# bela_expansion_card_2.net
KiCad netlist of a schematic drawn in Altium Designer
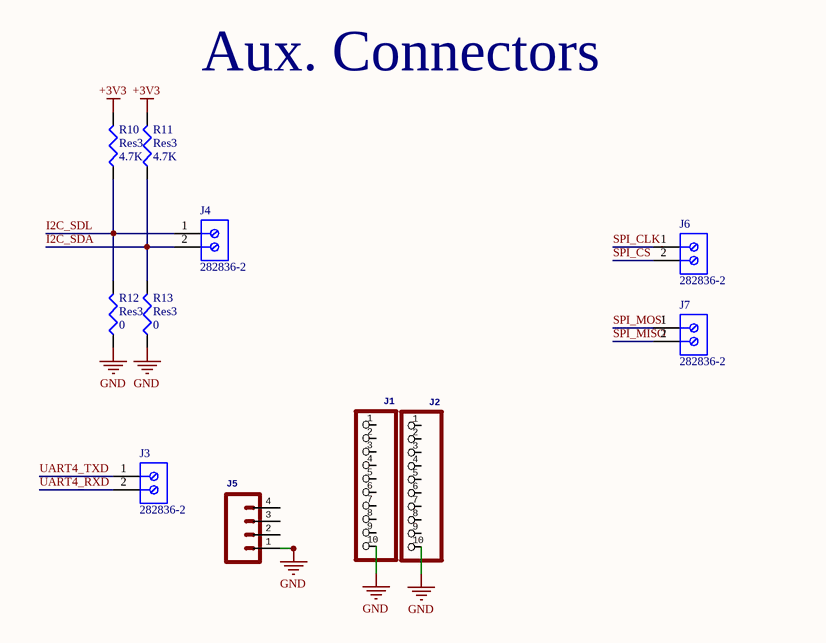
[diagram p0: bela_expansion_card_2.SchDoc]

(export (version "E")
  (design (tool "Eeschema 10.0.6"))
  (components
    (comp (ref "J1")
      (value "PINHD-1X10")
      (footprint "HDR1X10")
      (description "PIN HEADER")
      (fields (field (name "LIBRARYNAME") "pinhead"))
      (libsource (lib "pinhead") (part "PINHD-1X10"))
    )
    (comp (ref "J2")
      (value "PINHD-1X10")
      (footprint "HDR1X10")
      (description "PIN HEADER")
      (fields (field (name "LIBRARYNAME") "pinhead"))
      (libsource (lib "Miscellaneous Connectors") (part "PINHD-1X10"))
    )
    (comp (ref "J3")
      (value "282836-2")
      (footprint "TECO-282836-2_V")
      (description "Female Header, Pitch 5 mm, 1 x 2 Position, Height 10 mm, Tail Length 3.5 mm, Rohs, Bulk")
      (fields (field (name "VOLTAGE") "300V") (field (name "MANUFACTURER") "TE Connectivity"))
      (libsource (lib "Altium Content Vault") (part "CN-1P-F-TB2"))
    )
    (comp (ref "J4")
      (value "282836-2")
      (footprint "TECO-282836-2_V")
      (description "Female Header, Pitch 5 mm, 1 x 2 Position, Height 10 mm, Tail Length 3.5 mm, Rohs, Bulk")
      (fields (field (name "VOLTAGE") "300V") (field (name "MANUFACTURER") "TE Connectivity"))
      (libsource (lib "Altium Content Vault") (part "CN-1P-F-TB2"))
    )
    (comp (ref "J5")
      (value "M04PTH")
      (footprint "1X04")
      (libsource (lib "SparkFun-Connectors") (part "M04PTH"))
    )
    (comp (ref "J6")
      (value "282836-2")
      (footprint "TECO-282836-2_V")
      (description "Female Header, Pitch 5 mm, 1 x 2 Position, Height 10 mm, Tail Length 3.5 mm, Rohs, Bulk")
      (fields (field (name "VOLTAGE") "300V") (field (name "MANUFACTURER") "TE Connectivity"))
      (libsource (lib "Altium Content Vault") (part "CN-1P-F-TB2"))
    )
    (comp (ref "J7")
      (value "282836-2")
      (footprint "TECO-282836-2_V")
      (description "Female Header, Pitch 5 mm, 1 x 2 Position, Height 10 mm, Tail Length 3.5 mm, Rohs, Bulk")
      (fields (field (name "VOLTAGE") "300V") (field (name "MANUFACTURER") "TE Connectivity"))
      (libsource (lib "Altium Content Vault") (part "CN-1P-F-TB2"))
    )
    (comp (ref "R10")
      (value "Res3")
      (footprint "6-0805_L")
      (description "Resistor")
      (fields (field (name "ALTIUM_VALUE") "4.7K") (field (name "PUBLISHER") "Altium Limited"))
      (libsource (lib "Miscellaneous Devices") (part "Res3"))
    )
    (comp (ref "R11")
      (value "Res3")
      (footprint "6-0805_L")
      (description "Resistor")
      (fields (field (name "ALTIUM_VALUE") "4.7K") (field (name "PUBLISHER") "Altium Limited"))
      (libsource (lib "Miscellaneous Devices") (part "Res3"))
    )
    (comp (ref "R12")
      (value "Res3")
      (footprint "6-0805_L")
      (description "Resistor")
      (fields (field (name "ALTIUM_VALUE") "0") (field (name "PUBLISHER") "Altium Limited"))
      (libsource (lib "Miscellaneous Devices") (part "Res3"))
    )
    (comp (ref "R13")
      (value "Res3")
      (footprint "6-0805_L")
      (description "Resistor")
      (fields (field (name "ALTIUM_VALUE") "0") (field (name "PUBLISHER") "Altium Limited"))
      (libsource (lib "Miscellaneous Devices") (part "Res3"))
    )
  )
  (nets
    (net (code "1") (name "+3V3") (class "Default")
      (node (ref "R10") (pin "2") (pinfunction "2_2") (pintype "passive"))
      (node (ref "R11") (pin "2") (pinfunction "2_2") (pintype "passive"))
    )
    (net (code "2") (name "/I2C_SDA") (class "Default")
      (node (ref "J4") (pin "2") (pinfunction "2_2") (pintype "passive"))
      (node (ref "R11") (pin "1") (pinfunction "1_1") (pintype "passive"))
      (node (ref "R13") (pin "2") (pinfunction "2_2") (pintype "passive"))
    )
    (net (code "3") (name "/I2C_SDL") (class "Default")
      (node (ref "J4") (pin "1") (pinfunction "1_1") (pintype "passive"))
      (node (ref "R10") (pin "1") (pinfunction "1_1") (pintype "passive"))
      (node (ref "R12") (pin "2") (pinfunction "2_2") (pintype "passive"))
    )
    (net (code "4") (name "/SPI_CLK") (class "Default")
      (node (ref "J6") (pin "1") (pinfunction "1_1") (pintype "passive"))
    )
    (net (code "5") (name "/SPI_CS") (class "Default")
      (node (ref "J6") (pin "2") (pinfunction "2_2") (pintype "passive"))
    )
    (net (code "6") (name "/SPI_MISO") (class "Default")
      (node (ref "J7") (pin "2") (pinfunction "2_2") (pintype "passive"))
    )
    (net (code "7") (name "/SPI_MOSI") (class "Default")
      (node (ref "J7") (pin "1") (pinfunction "1_1") (pintype "passive"))
    )
    (net (code "8") (name "/UART4_RXD") (class "Default")
      (node (ref "J3") (pin "2") (pinfunction "2_2") (pintype "passive"))
    )
    (net (code "9") (name "/UART4_TXD") (class "Default")
      (node (ref "J3") (pin "1") (pinfunction "1_1") (pintype "passive"))
    )
    (net (code "10") (name "GND") (class "Default")
      (node (ref "J1") (pin "10") (pinfunction "10_10") (pintype "passive"))
      (node (ref "J2") (pin "10") (pinfunction "10_10") (pintype "passive"))
      (node (ref "J5") (pin "1") (pinfunction "1_1") (pintype "passive"))
      (node (ref "R12") (pin "1") (pinfunction "1_1") (pintype "passive"))
      (node (ref "R13") (pin "1") (pinfunction "1_1") (pintype "passive"))
    )
    (net (code "11") (name "unconnected-(J1-Pad1)") (class "Default")
      (node (ref "J1") (pin "1") (pinfunction "1_1") (pintype "passive"))
    )
    (net (code "12") (name "unconnected-(J1-Pad2)") (class "Default")
      (node (ref "J1") (pin "2") (pinfunction "2_2") (pintype "passive"))
    )
    (net (code "13") (name "unconnected-(J1-Pad3)") (class "Default")
      (node (ref "J1") (pin "3") (pinfunction "3_3") (pintype "passive"))
    )
    (net (code "14") (name "unconnected-(J1-Pad4)") (class "Default")
      (node (ref "J1") (pin "4") (pinfunction "4_4") (pintype "passive"))
    )
    (net (code "15") (name "unconnected-(J1-Pad5)") (class "Default")
      (node (ref "J1") (pin "5") (pinfunction "5_5") (pintype "passive"))
    )
    (net (code "16") (name "unconnected-(J1-Pad6)") (class "Default")
      (node (ref "J1") (pin "6") (pinfunction "6_6") (pintype "passive"))
    )
    (net (code "17") (name "unconnected-(J1-Pad7)") (class "Default")
      (node (ref "J1") (pin "7") (pinfunction "7_7") (pintype "passive"))
    )
    (net (code "18") (name "unconnected-(J1-Pad8)") (class "Default")
      (node (ref "J1") (pin "8") (pinfunction "8_8") (pintype "passive"))
    )
    (net (code "19") (name "unconnected-(J1-Pad9)") (class "Default")
      (node (ref "J1") (pin "9") (pinfunction "9_9") (pintype "passive"))
    )
    (net (code "20") (name "unconnected-(J2-Pad1)") (class "Default")
      (node (ref "J2") (pin "1") (pinfunction "1_1") (pintype "passive"))
    )
    (net (code "21") (name "unconnected-(J2-Pad2)") (class "Default")
      (node (ref "J2") (pin "2") (pinfunction "2_2") (pintype "passive"))
    )
    (net (code "22") (name "unconnected-(J2-Pad3)") (class "Default")
      (node (ref "J2") (pin "3") (pinfunction "3_3") (pintype "passive"))
    )
    (net (code "23") (name "unconnected-(J2-Pad4)") (class "Default")
      (node (ref "J2") (pin "4") (pinfunction "4_4") (pintype "passive"))
    )
    (net (code "24") (name "unconnected-(J2-Pad5)") (class "Default")
      (node (ref "J2") (pin "5") (pinfunction "5_5") (pintype "passive"))
    )
    (net (code "25") (name "unconnected-(J2-Pad6)") (class "Default")
      (node (ref "J2") (pin "6") (pinfunction "6_6") (pintype "passive"))
    )
    (net (code "26") (name "unconnected-(J2-Pad7)") (class "Default")
      (node (ref "J2") (pin "7") (pinfunction "7_7") (pintype "passive"))
    )
    (net (code "27") (name "unconnected-(J2-Pad8)") (class "Default")
      (node (ref "J2") (pin "8") (pinfunction "8_8") (pintype "passive"))
    )
    (net (code "28") (name "unconnected-(J2-Pad9)") (class "Default")
      (node (ref "J2") (pin "9") (pinfunction "9_9") (pintype "passive"))
    )
    (net (code "29") (name "unconnected-(J5-Pad2)") (class "Default")
      (node (ref "J5") (pin "2") (pinfunction "2_2") (pintype "passive"))
    )
    (net (code "30") (name "unconnected-(J5-Pad3)") (class "Default")
      (node (ref "J5") (pin "3") (pinfunction "3_3") (pintype "passive"))
    )
    (net (code "31") (name "unconnected-(J5-Pad4)") (class "Default")
      (node (ref "J5") (pin "4") (pinfunction "4_4") (pintype "passive"))
    )
  )
)
